# Power_Embedded_Board_Top.net
KiCad netlist of a schematic drawn in Altium Designer
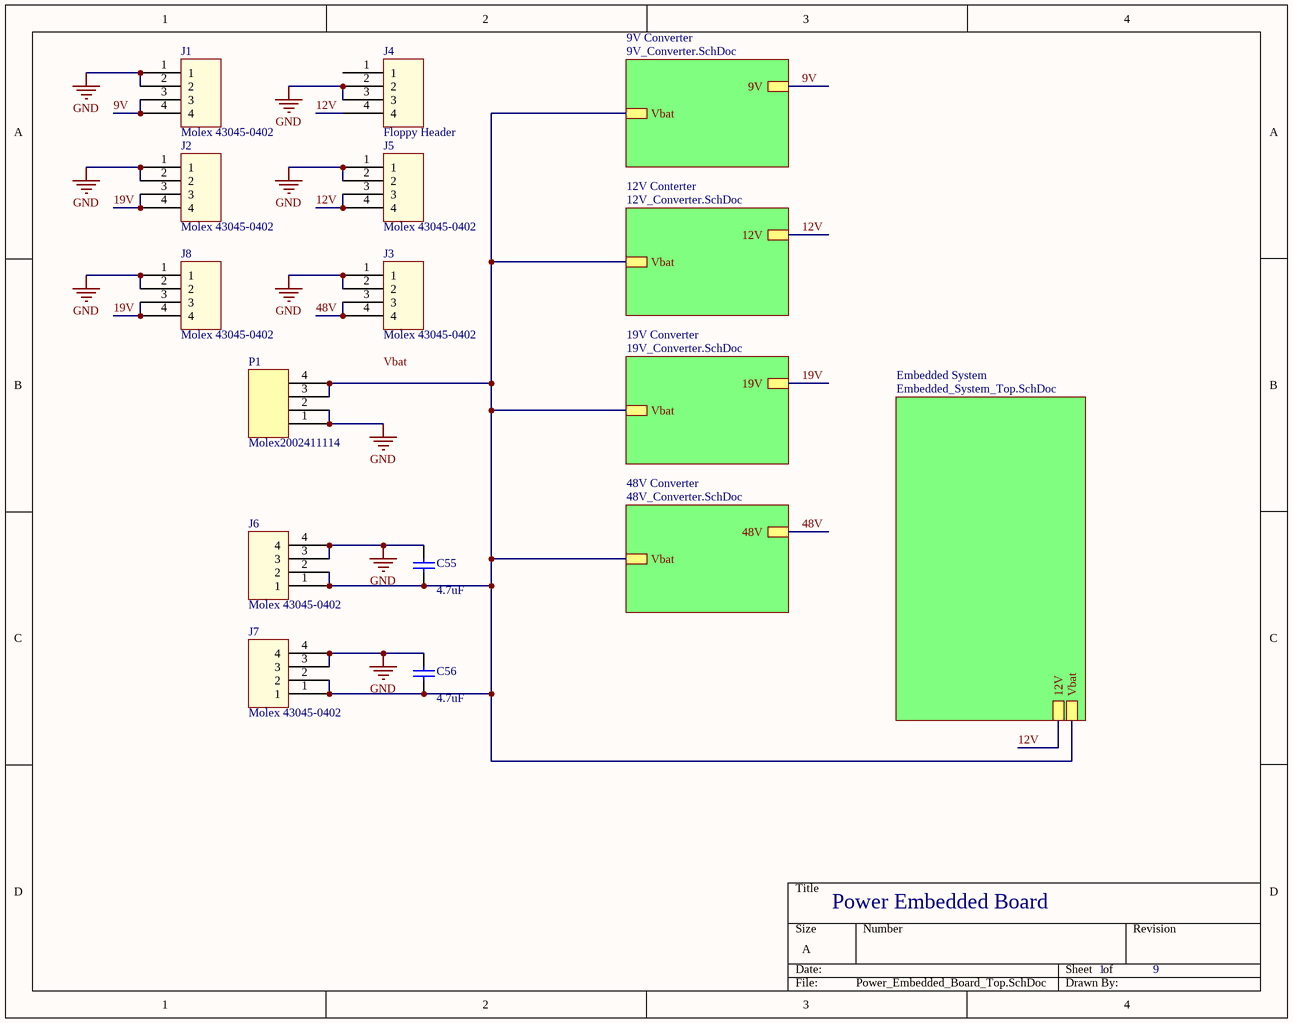
[diagram p0: Power_Embedded_Board_Top.SchDoc]

(export (version "E")
  (design (tool "Eeschema 10.0.6"))
  (components
    (comp (ref "C55")
      (value "4.7uF")
      (footprint "C1210")
      (description "Capacitor (Semiconductor SIM Model)")
      (fields (field (name "Comment") "HMK325C7475KN-TE") (field (name "PUBLISHER") "Altium Limited"))
      (libsource (lib "Miscellaneous Devices") (part "Cap Semi"))
    )
    (comp (ref "C56")
      (value "4.7uF")
      (footprint "C1210")
      (description "Capacitor (Semiconductor SIM Model)")
      (fields (field (name "Comment") "HMK325C7475KN-TE") (field (name "PUBLISHER") "Altium Limited"))
      (libsource (lib "Miscellaneous Devices") (part "Cap Semi"))
    )
    (comp (ref "J1")
      (value "Molex 43045-0402")
      (footprint "Molex43045-0402")
      (libsource (lib "Power_Embedded_Board_Library") (part "Molex43045-0402"))
    )
    (comp (ref "J2")
      (value "Molex 43045-0402")
      (footprint "Molex43045-0402")
      (libsource (lib "Power_Embedded_Board_Library") (part "Molex43045-0402"))
    )
    (comp (ref "J3")
      (value "Molex 43045-0402")
      (footprint "Molex43045-0402")
      (libsource (lib "Power_Embedded_Board_Library") (part "Molex43045-0402"))
    )
    (comp (ref "J4")
      (value "Floppy Header")
      (footprint "Header 1x4 12V")
      (libsource (lib "Power_Embedded_Board_Library") (part "Molex43045-0402"))
    )
    (comp (ref "J5")
      (value "Molex 43045-0402")
      (footprint "Molex43045-0402")
      (libsource (lib "Power_Embedded_Board_Library") (part "Molex43045-0402"))
    )
    (comp (ref "J6")
      (value "Molex 43045-0402")
      (footprint "Molex43045-0402")
      (libsource (lib "") (part "Molex43045-0402_1"))
    )
    (comp (ref "J7")
      (value "Molex 43045-0402")
      (footprint "Molex43045-0402")
      (libsource (lib "") (part "Molex43045-0402_1"))
    )
    (comp (ref "J8")
      (value "Molex 43045-0402")
      (footprint "Molex43045-0402")
      (libsource (lib "Power_Embedded_Board_Library") (part "Molex43045-0402"))
    )
    (comp (ref "P1")
      (value "Molex2002411114")
      (footprint "Molex2002411114")
      (libsource (lib "Power_Embedded_Board_Library") (part "Molex2002411114"))
    )
  )
  (nets
    (net (code "1") (name "/9V") (class "Default")
      (node (ref "J1") (pin "3") (pinfunction "3_3") (pintype "passive"))
      (node (ref "J1") (pin "4") (pinfunction "4_4") (pintype "passive"))
    )
    (net (code "2") (name "/12V") (class "Default")
      (node (ref "J4") (pin "4") (pinfunction "4_4") (pintype "passive"))
      (node (ref "J5") (pin "3") (pinfunction "3_3") (pintype "passive"))
      (node (ref "J5") (pin "4") (pinfunction "4_4") (pintype "passive"))
    )
    (net (code "3") (name "/19V") (class "Default")
      (node (ref "J2") (pin "3") (pinfunction "3_3") (pintype "passive"))
      (node (ref "J2") (pin "4") (pinfunction "4_4") (pintype "passive"))
      (node (ref "J8") (pin "3") (pinfunction "3_3") (pintype "passive"))
      (node (ref "J8") (pin "4") (pinfunction "4_4") (pintype "passive"))
    )
    (net (code "4") (name "/48V") (class "Default")
      (node (ref "J3") (pin "3") (pinfunction "3_3") (pintype "passive"))
      (node (ref "J3") (pin "4") (pinfunction "4_4") (pintype "passive"))
    )
    (net (code "6") (name "/Vbat_1") (class "Default")
      (node (ref "C55") (pin "1") (pinfunction "1_1") (pintype "passive"))
      (node (ref "C56") (pin "1") (pinfunction "1_1") (pintype "passive"))
      (node (ref "J6") (pin "1") (pinfunction "1_1") (pintype "passive"))
      (node (ref "J6") (pin "2") (pinfunction "2_2") (pintype "passive"))
      (node (ref "J7") (pin "1") (pinfunction "1_1") (pintype "passive"))
      (node (ref "J7") (pin "2") (pinfunction "2_2") (pintype "passive"))
      (node (ref "P1") (pin "3") (pintype "power_in"))
      (node (ref "P1") (pin "4") (pintype "power_in"))
    )
    (net (code "7") (name "GND") (class "Default")
      (node (ref "C55") (pin "2") (pinfunction "2_2") (pintype "passive"))
      (node (ref "C56") (pin "2") (pinfunction "2_2") (pintype "passive"))
      (node (ref "J1") (pin "1") (pinfunction "1_1") (pintype "passive"))
      (node (ref "J1") (pin "2") (pinfunction "2_2") (pintype "passive"))
      (node (ref "J2") (pin "1") (pinfunction "1_1") (pintype "passive"))
      (node (ref "J2") (pin "2") (pinfunction "2_2") (pintype "passive"))
      (node (ref "J3") (pin "1") (pinfunction "1_1") (pintype "passive"))
      (node (ref "J3") (pin "2") (pinfunction "2_2") (pintype "passive"))
      (node (ref "J4") (pin "2") (pinfunction "2_2") (pintype "passive"))
      (node (ref "J4") (pin "3") (pinfunction "3_3") (pintype "passive"))
      (node (ref "J5") (pin "1") (pinfunction "1_1") (pintype "passive"))
      (node (ref "J5") (pin "2") (pinfunction "2_2") (pintype "passive"))
      (node (ref "J6") (pin "3") (pinfunction "3_3") (pintype "passive"))
      (node (ref "J6") (pin "4") (pinfunction "4_4") (pintype "passive"))
      (node (ref "J7") (pin "3") (pinfunction "3_3") (pintype "passive"))
      (node (ref "J7") (pin "4") (pinfunction "4_4") (pintype "passive"))
      (node (ref "J8") (pin "1") (pinfunction "1_1") (pintype "passive"))
      (node (ref "J8") (pin "2") (pinfunction "2_2") (pintype "passive"))
      (node (ref "P1") (pin "1") (pintype "power_in"))
      (node (ref "P1") (pin "2") (pintype "power_in"))
    )
    (net (code "8") (name "unconnected-(J4-Pad1)") (class "Default")
      (node (ref "J4") (pin "1") (pinfunction "1_1") (pintype "passive"))
    )
  )
)
